# sepic12-12.net
KiCad netlist of a schematic drawn in Altium Designer
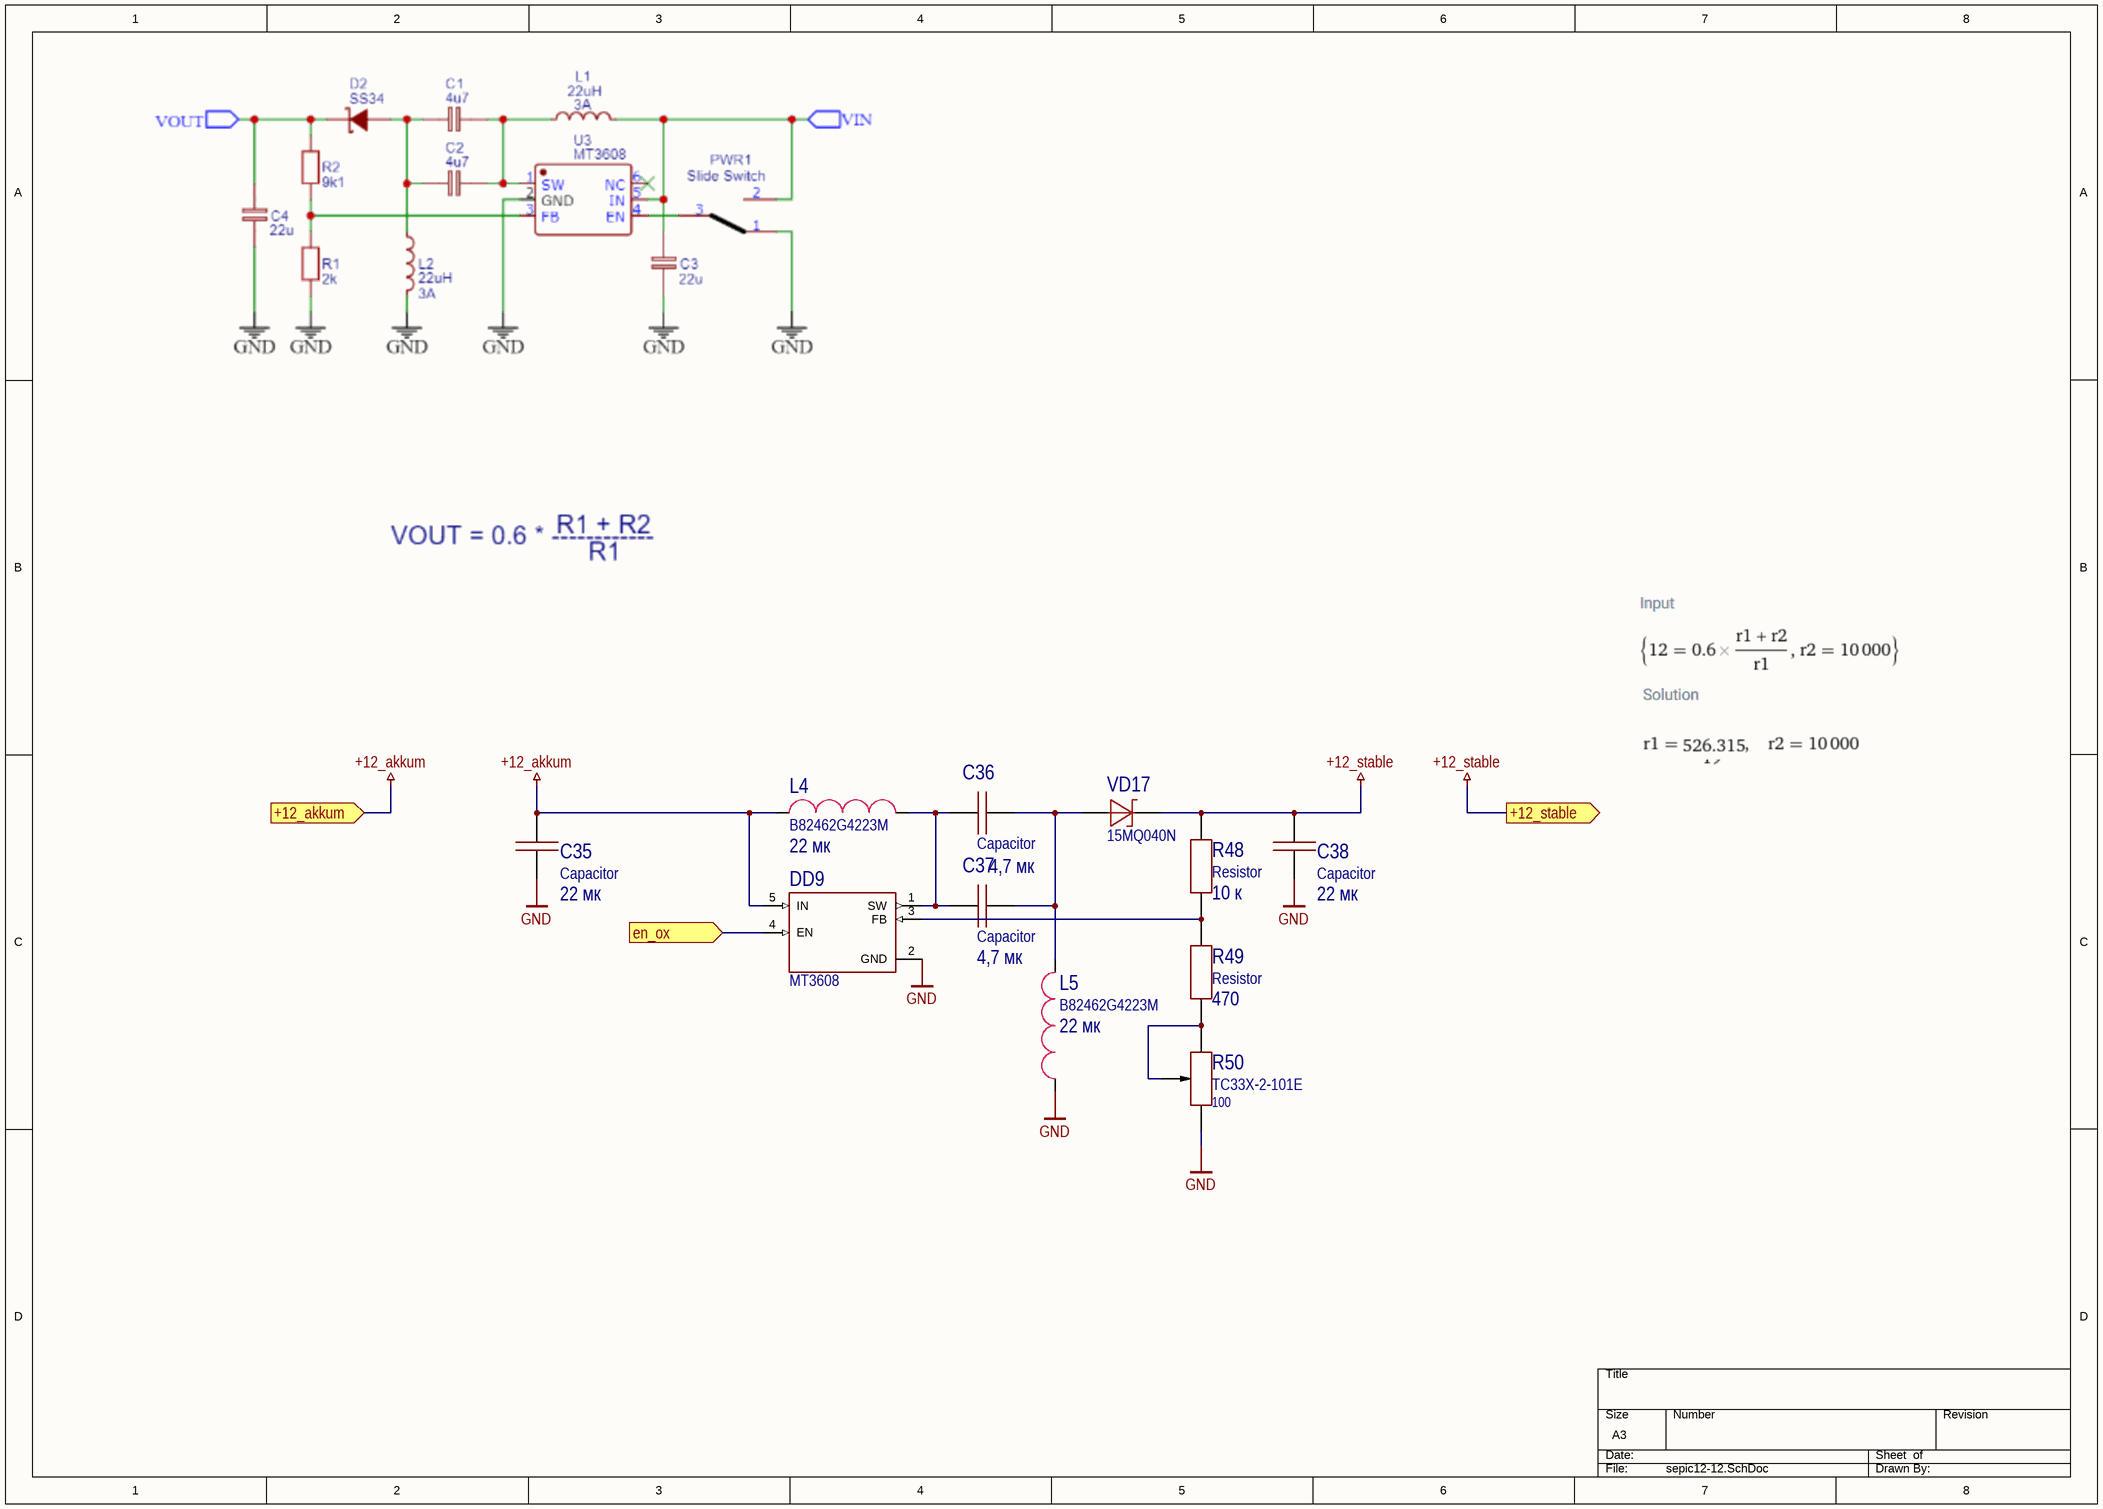
[diagram p0: sepic12-12.SchDoc]

(export (version "E")
  (design (tool "Eeschema 10.0.6"))
  (components
    (comp (ref "C35")
      (value "Capacitor")
      (footprint "1210C")
      (description "Конденсатор")
      (fields
        (field (name "ALTIUM_VALUE") "22 мк")
        (field (name "PART NUMBER") "Capacitor_22u_10_25V_X7R_1210C")
        (field (name "TOLERANCE") "0,1")
      )
      (libsource (lib "Hydrolib") (part "Capacitor"))
    )
    (comp (ref "C36")
      (value "Capacitor")
      (footprint "1206C")
      (description "Конденсатор")
      (fields
        (field (name "ALTIUM_VALUE") "4,7 мк")
        (field (name "PART NUMBER") "Capacitor_4,7u_10_50V_X7R_1206C")
        (field (name "TOLERANCE") "0,1")
      )
      (libsource (lib "Hydrolib") (part "Capacitor"))
    )
    (comp (ref "C37")
      (value "Capacitor")
      (footprint "1206C")
      (description "Конденсатор")
      (fields
        (field (name "ALTIUM_VALUE") "4,7 мк")
        (field (name "PART NUMBER") "Capacitor_4,7u_10_50V_X7R_1206C")
        (field (name "TOLERANCE") "0,1")
      )
      (libsource (lib "Hydrolib") (part "Capacitor"))
    )
    (comp (ref "C38")
      (value "Capacitor")
      (footprint "1210C")
      (description "Конденсатор")
      (fields
        (field (name "ALTIUM_VALUE") "22 мк")
        (field (name "PART NUMBER") "Capacitor_22u_10_25V_X7R_1210C")
        (field (name "TOLERANCE") "0,1")
      )
      (libsource (lib "Hydrolib") (part "Capacitor"))
    )
    (comp (ref "DD9")
      (value "MT3608")
      (footprint "SOT23-6")
      (description "Повышающий/SEPIC DC-DC преобразователь 2А 1.2МГц")
      (libsource (lib "Hydrolib") (part "MT3608"))
    )
    (comp (ref "L4")
      (value "B82462G4223M")
      (footprint "B82462G4")
      (description "ЧИП-индуктивность 22мкГн, 1.05A, ±20% катушка")
      (fields (field (name "ALTIUM_VALUE") "22 мк"))
      (libsource (lib "Hydrolib") (part "Inductance"))
    )
    (comp (ref "L5")
      (value "B82462G4223M")
      (footprint "B82462G4")
      (description "ЧИП-индуктивность 22мкГн, 1.05A, ±20% катушка")
      (fields (field (name "ALTIUM_VALUE") "22 мк"))
      (libsource (lib "Hydrolib") (part "Inductance"))
    )
    (comp (ref "R48")
      (value "Resistor")
      (footprint "0603R")
      (description "Резистор номиналом 10 кОм и точностью 1%")
      (fields
        (field (name "ALTIUM_VALUE") "10 к")
        (field (name "PART NUMBER") "Resistor_10k_1_0603")
        (field (name "TOLERANCE") "1%")
      )
      (libsource (lib "Hydrolib") (part "Resistor"))
    )
    (comp (ref "R49")
      (value "Resistor")
      (footprint "0603R")
      (description "Резистор номиналом 470 Ом и точностью 1%")
      (fields
        (field (name "ALTIUM_VALUE") "470")
        (field (name "PART NUMBER") "Resistor_470_1_0603")
        (field (name "TOLERANCE") "1%")
      )
      (libsource (lib "Hydrolib") (part "Resistor"))
    )
    (comp (ref "R50")
      (value "TC33X-2-101E")
      (footprint "3mm_trim")
      (description "Потенциометр керметный 100 Ом 0.1Вт для поверхностного монтажа")
      (fields (field (name "ALTIUM_VALUE") "100") (field (name "TOLERANCE") "50%"))
      (libsource (lib "Hydrolib") (part "trim_res"))
    )
    (comp (ref "VD17")
      (value "15MQ040N")
      (footprint "SMA")
      (description "Диод шоттки на 40 В, ном. ток 2.1 А")
      (libsource (lib "Hydrolib") (part "Schottky_diode"))
    )
  )
  (nets
    (net (code "1") (name "+12_akkum") (class "Default")
      (node (ref "C35") (pin "2") (pinfunction "2_2") (pintype "passive"))
      (node (ref "DD9") (pin "5") (pinfunction "IN_5") (pintype "input"))
      (node (ref "L4") (pin "1") (pinfunction "1_1") (pintype "passive"))
    )
    (net (code "2") (name "+12_stable") (class "Default")
      (node (ref "C38") (pin "2") (pinfunction "2_2") (pintype "passive"))
      (node (ref "R48") (pin "2") (pinfunction "2_2") (pintype "passive"))
      (node (ref "VD17") (pin "2") (pinfunction "2_2") (pintype "passive"))
    )
    (net (code "3") (name "/en_ox") (class "Default")
      (node (ref "DD9") (pin "4") (pinfunction "EN_4") (pintype "input"))
    )
    (net (code "4") (name "GND") (class "Default")
      (node (ref "C35") (pin "1") (pinfunction "1_1") (pintype "passive"))
      (node (ref "C38") (pin "1") (pinfunction "1_1") (pintype "passive"))
      (node (ref "DD9") (pin "2") (pinfunction "GND_2") (pintype "power_in"))
      (node (ref "L5") (pin "1") (pinfunction "1_1") (pintype "passive"))
      (node (ref "R50") (pin "1") (pinfunction "1_1") (pintype "passive"))
    )
    (net (code "5") (name "Net-(C36-Pad2)") (class "Default")
      (node (ref "C36") (pin "2") (pinfunction "2_2") (pintype "passive"))
      (node (ref "C37") (pin "2") (pinfunction "2_2") (pintype "passive"))
      (node (ref "L5") (pin "2") (pinfunction "2_2") (pintype "passive"))
      (node (ref "VD17") (pin "1") (pinfunction "1_1") (pintype "passive"))
    )
    (net (code "6") (name "Net-(DD9-FB)") (class "Default")
      (node (ref "DD9") (pin "3") (pinfunction "FB_3") (pintype "input"))
      (node (ref "R48") (pin "1") (pinfunction "1_1") (pintype "passive"))
      (node (ref "R49") (pin "2") (pinfunction "2_2") (pintype "passive"))
    )
    (net (code "7") (name "Net-(DD9-SW)") (class "Default")
      (node (ref "C36") (pin "1") (pinfunction "1_1") (pintype "passive"))
      (node (ref "C37") (pin "1") (pinfunction "1_1") (pintype "passive"))
      (node (ref "DD9") (pin "1") (pinfunction "SW_1") (pintype "output"))
      (node (ref "L4") (pin "2") (pinfunction "2_2") (pintype "passive"))
    )
    (net (code "8") (name "Net-(R49-Pad1)") (class "Default")
      (node (ref "R49") (pin "1") (pinfunction "1_1") (pintype "passive"))
      (node (ref "R50") (pin "2") (pinfunction "2_2") (pintype "passive"))
      (node (ref "R50") (pin "3") (pinfunction "3_3") (pintype "passive"))
    )
  )
)
